# psu-digital.net
KiCad netlist of a schematic drawn in EAGLE
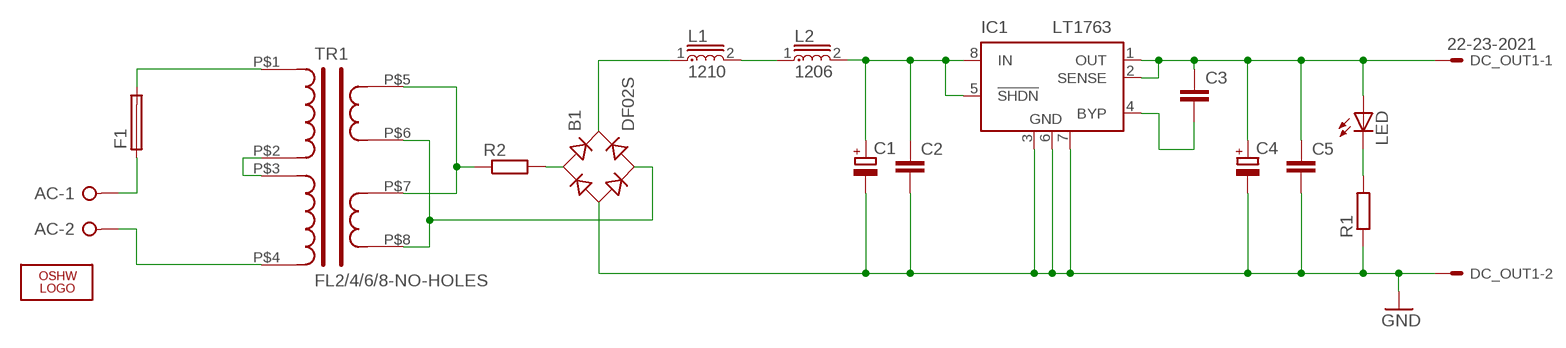
[diagram p0: schematic, sheet 1]

(export (version "E")
  (design (tool "Eeschema 10.0.6"))
  (components
    (comp (ref "AC")
      (value "W237-02P")
      (footprint "eagle-import:W237-132")
      (libsource (lib "eagle-import") (part "W237-02P"))
    )
    (comp (ref "B1")
      (value "DF02S")
      (footprint "eagle-import:DFS")
      (libsource (lib "eagle-import") (part "DFS02"))
    )
    (comp (ref "C1")
      (value "CPOL-EUE7.5-16")
      (footprint "eagle-import:E7,5-16")
      (libsource (lib "eagle-import") (part "CPOL-EUE7.5-16"))
    )
    (comp (ref "C2")
      (value "C-EUC1206")
      (footprint "eagle-import:C1206")
      (libsource (lib "eagle-import") (part "C-EUC1206"))
    )
    (comp (ref "C3")
      (value "C-EUC1206")
      (footprint "eagle-import:C1206")
      (libsource (lib "eagle-import") (part "C-EUC1206"))
    )
    (comp (ref "C4")
      (value "CPOL-EUD")
      (footprint "eagle-import:PANASONIC_D")
      (libsource (lib "eagle-import") (part "CPOL-EUD"))
    )
    (comp (ref "C5")
      (value "C-EUC1206")
      (footprint "eagle-import:C1206")
      (libsource (lib "eagle-import") (part "C-EUC1206"))
    )
    (comp (ref "DC_OUT1")
      (value "22-23-2021")
      (footprint "eagle-import:22-23-2021")
      (fields (field (name "MF") "MOLEX"))
      (libsource (lib "eagle-import") (part "22-23-2021"))
    )
    (comp (ref "F1")
      (value "GSH15")
      (footprint "eagle-import:GSH15")
      (fields (field (name "MPN") "64900001039"))
      (libsource (lib "eagle-import") (part "GSH15"))
    )
    (comp (ref "IC1")
      (value "LT1763")
      (footprint "eagle-import:SOIC8")
      (fields (field (name "MPN") "LT1763CS8-3.3"))
      (libsource (lib "eagle-import") (part "LT1763CS8-3.3"))
    )
    (comp (ref "L1")
      (value "1210")
      (footprint "eagle-import:1210")
      (libsource (lib "eagle-import") (part "1210"))
    )
    (comp (ref "L2")
      (value "1206")
      (footprint "eagle-import:1206")
      (libsource (lib "eagle-import") (part "1206"))
    )
    (comp (ref "LED")
      (value "LEDCHIPLED_1206")
      (footprint "eagle-import:CHIPLED_1206")
      (libsource (lib "eagle-import") (part "LEDCHIPLED_1206"))
    )
    (comp (ref "LOGO1")
      (value "OSHW_LOGO_FILLX0200-NT")
      (footprint "eagle-import:OSHW_FILLX200_NOTEXT")
      (libsource (lib "eagle-import") (part "OSHW_LOGO_FILLX0200-NT"))
    )
    (comp (ref "R1")
      (value "R-EU_R1206")
      (footprint "eagle-import:R1206")
      (libsource (lib "eagle-import") (part "R-EU_R1206"))
    )
    (comp (ref "R2")
      (value "R-EU_R1210")
      (footprint "eagle-import:R1210")
      (libsource (lib "eagle-import") (part "R-EU_R1210"))
    )
    (comp (ref "TR1")
      (value "FL2/4/6/8-NO-HOLES")
      (footprint "eagle-import:FL2_4_6_8-NO-HOLES")
      (libsource (lib "eagle-import") (part "FL2/4/6/8-NO-HOLES"))
    )
  )
  (nets
    (net (code "1") (name "GND") (class "Default")
      (node (ref "B1") (pin "-") (pinfunction "-_-") (pintype "passive"))
      (node (ref "C1") (pin "-") (pinfunction "-_-") (pintype "passive"))
      (node (ref "C2") (pin "2") (pinfunction "2_2") (pintype "passive"))
      (node (ref "C4") (pin "-") (pinfunction "-_-") (pintype "passive"))
      (node (ref "C5") (pin "2") (pinfunction "2_2") (pintype "passive"))
      (node (ref "DC_OUT1") (pin "2") (pinfunction "S_2") (pintype "passive"))
      (node (ref "IC1") (pin "3") (pinfunction "GND_3") (pintype "power_in"))
      (node (ref "IC1") (pin "6") (pinfunction "GND_6") (pintype "power_in"))
      (node (ref "IC1") (pin "7") (pinfunction "GND_7") (pintype "power_in"))
      (node (ref "R1") (pin "1") (pinfunction "1_1") (pintype "passive"))
    )
    (net (code "2") (name "Net-(ACA-KL)") (class "Default")
      (node (ref "AC") (pin "1") (pinfunction "KL_1") (pintype "passive"))
      (node (ref "F1") (pin "1") (pinfunction "1_1") (pintype "passive"))
    )
    (net (code "3") (name "Net-(ACB-KL)") (class "Default")
      (node (ref "AC") (pin "2") (pinfunction "KL_2") (pintype "passive"))
      (node (ref "TR1") (pin "P$4") (pinfunction "PRI2B_P$4") (pintype "passive"))
    )
    (net (code "4") (name "Net-(B1-Pad+)") (class "Default")
      (node (ref "B1") (pin "+") (pinfunction "+_+") (pintype "passive"))
      (node (ref "L1") (pin "1") (pinfunction "1_1") (pintype "passive"))
    )
    (net (code "5") (name "Net-(B1-PadAC1)") (class "Default")
      (node (ref "B1") (pin "AC1") (pinfunction "AC1_AC1") (pintype "passive"))
      (node (ref "R2") (pin "2") (pinfunction "2_2") (pintype "passive"))
    )
    (net (code "6") (name "Net-(DC_OUT1A-S)") (class "Default")
      (node (ref "C3") (pin "1") (pinfunction "1_1") (pintype "passive"))
      (node (ref "C4") (pin "+") (pinfunction "+_+") (pintype "passive"))
      (node (ref "C5") (pin "1") (pinfunction "1_1") (pintype "passive"))
      (node (ref "DC_OUT1") (pin "1") (pinfunction "S_1") (pintype "passive"))
      (node (ref "IC1") (pin "1") (pinfunction "OUT_1") (pintype "passive"))
      (node (ref "IC1") (pin "2") (pinfunction "SENSE_2") (pintype "input"))
      (node (ref "LED") (pin "A") (pinfunction "A_A") (pintype "passive"))
    )
    (net (code "7") (name "Net-(IC1-BYP)") (class "Default")
      (node (ref "C3") (pin "2") (pinfunction "2_2") (pintype "passive"))
      (node (ref "IC1") (pin "4") (pinfunction "BYP_4") (pintype "input"))
    )
    (net (code "8") (name "Net-(IC1-IN)") (class "Default")
      (node (ref "C1") (pin "+") (pinfunction "+_+") (pintype "passive"))
      (node (ref "C2") (pin "1") (pinfunction "1_1") (pintype "passive"))
      (node (ref "IC1") (pin "5") (pinfunction "~{SHDN}_5") (pintype "input"))
      (node (ref "IC1") (pin "8") (pinfunction "IN_8") (pintype "input"))
      (node (ref "L2") (pin "2") (pinfunction "2_2") (pintype "passive"))
    )
    (net (code "9") (name "Net-(L1-Pad2)") (class "Default")
      (node (ref "L1") (pin "2") (pinfunction "2_2") (pintype "passive"))
      (node (ref "L2") (pin "1") (pinfunction "1_1") (pintype "passive"))
    )
    (net (code "10") (name "Net-(LED-PadC)") (class "Default")
      (node (ref "LED") (pin "C") (pinfunction "C_C") (pintype "passive"))
      (node (ref "R1") (pin "2") (pinfunction "2_2") (pintype "passive"))
    )
    (net (code "11") (name "Net-(TR1-PRI1A)") (class "Default")
      (node (ref "F1") (pin "2") (pinfunction "2_2") (pintype "passive"))
      (node (ref "TR1") (pin "P$1") (pinfunction "PRI1A_P$1") (pintype "passive"))
    )
    (net (code "12") (name "Net-(TR1-PRI1B)") (class "Default")
      (node (ref "TR1") (pin "P$2") (pinfunction "PRI1B_P$2") (pintype "passive"))
      (node (ref "TR1") (pin "P$3") (pinfunction "PRI2A_P$3") (pintype "passive"))
    )
    (net (code "13") (name "Net-(TR1-SEC1A)") (class "Default")
      (node (ref "R2") (pin "1") (pinfunction "1_1") (pintype "passive"))
      (node (ref "TR1") (pin "P$5") (pinfunction "SEC1A_P$5") (pintype "passive"))
      (node (ref "TR1") (pin "P$7") (pinfunction "SEC2A_P$7") (pintype "passive"))
    )
    (net (code "14") (name "Net-(TR1-SEC1B)") (class "Default")
      (node (ref "B1") (pin "AC2") (pinfunction "AC2_AC2") (pintype "passive"))
      (node (ref "TR1") (pin "P$6") (pinfunction "SEC1B_P$6") (pintype "passive"))
      (node (ref "TR1") (pin "P$8") (pinfunction "SEC2B_P$8") (pintype "passive"))
    )
  )
)
